# main.net
KiCad netlist of a schematic drawn in EAGLE
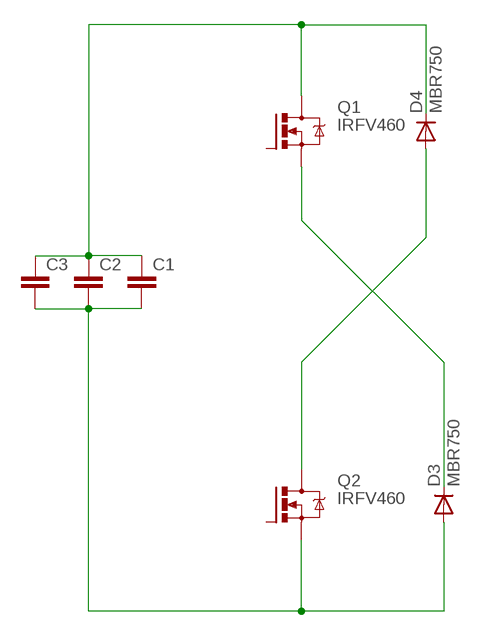
[diagram p0: schematic, sheet 1]

(export (version "E")
  (design (tool "Eeschema 10.0.6"))
  (components
    (comp (ref "C1")
      (value "C-EU375-203X418")
      (footprint "eagle-import:C375-203X418")
      (libsource (lib "eagle-import") (part "C-EU375-203X418"))
    )
    (comp (ref "C2")
      (value "C-EU375-203X418")
      (footprint "eagle-import:C375-203X418")
      (libsource (lib "eagle-import") (part "C-EU375-203X418"))
    )
    (comp (ref "C3")
      (value "C-EU375-203X418")
      (footprint "eagle-import:C375-203X418")
      (libsource (lib "eagle-import") (part "C-EU375-203X418"))
    )
    (comp (ref "D3")
      (value "MBR750")
      (footprint "eagle-import:TO220AC")
      (libsource (lib "eagle-import") (part "MBR750"))
    )
    (comp (ref "D4")
      (value "MBR750")
      (footprint "eagle-import:TO220AC")
      (libsource (lib "eagle-import") (part "MBR750"))
    )
    (comp (ref "Q1")
      (value "IRFV460")
      (footprint "eagle-import:TO258AA")
      (libsource (lib "eagle-import") (part "IRFV460"))
    )
    (comp (ref "Q2")
      (value "IRFV460")
      (footprint "eagle-import:TO258AA")
      (libsource (lib "eagle-import") (part "IRFV460"))
    )
  )
  (nets
    (net (code "1") (name "Net-(Q1-D)") (class "Default")
      (node (ref "C1") (pin "1") (pinfunction "1_1") (pintype "passive"))
      (node (ref "C2") (pin "1") (pinfunction "1_1") (pintype "passive"))
      (node (ref "C3") (pin "1") (pinfunction "1_1") (pintype "passive"))
      (node (ref "D4") (pin "C") (pinfunction "C_C") (pintype "passive"))
      (node (ref "Q1") (pin "1-D") (pinfunction "D_1-D") (pintype "passive"))
    )
    (net (code "2") (name "Net-(Q1-S)") (class "Default")
      (node (ref "D3") (pin "C") (pinfunction "C_C") (pintype "passive"))
      (node (ref "Q1") (pin "2-S") (pinfunction "S_2-S") (pintype "passive"))
    )
    (net (code "3") (name "Net-(Q2-D)") (class "Default")
      (node (ref "D4") (pin "A") (pinfunction "A_A") (pintype "passive"))
      (node (ref "Q2") (pin "1-D") (pinfunction "D_1-D") (pintype "passive"))
    )
    (net (code "4") (name "Net-(Q2-S)") (class "Default")
      (node (ref "C1") (pin "2") (pinfunction "2_2") (pintype "passive"))
      (node (ref "C2") (pin "2") (pinfunction "2_2") (pintype "passive"))
      (node (ref "C3") (pin "2") (pinfunction "2_2") (pintype "passive"))
      (node (ref "D3") (pin "A") (pinfunction "A_A") (pintype "passive"))
      (node (ref "Q2") (pin "2-S") (pinfunction "S_2-S") (pintype "passive"))
    )
    (net (code "5") (name "unconnected-(Q1-G-Pad3-G)") (class "Default")
      (node (ref "Q1") (pin "3-G") (pinfunction "G_3-G") (pintype "passive"))
    )
    (net (code "6") (name "unconnected-(Q2-G-Pad3-G)") (class "Default")
      (node (ref "Q2") (pin "3-G") (pinfunction "G_3-G") (pintype "passive"))
    )
  )
)
